# MainBoard.net
KiCad netlist of a schematic drawn in EAGLE
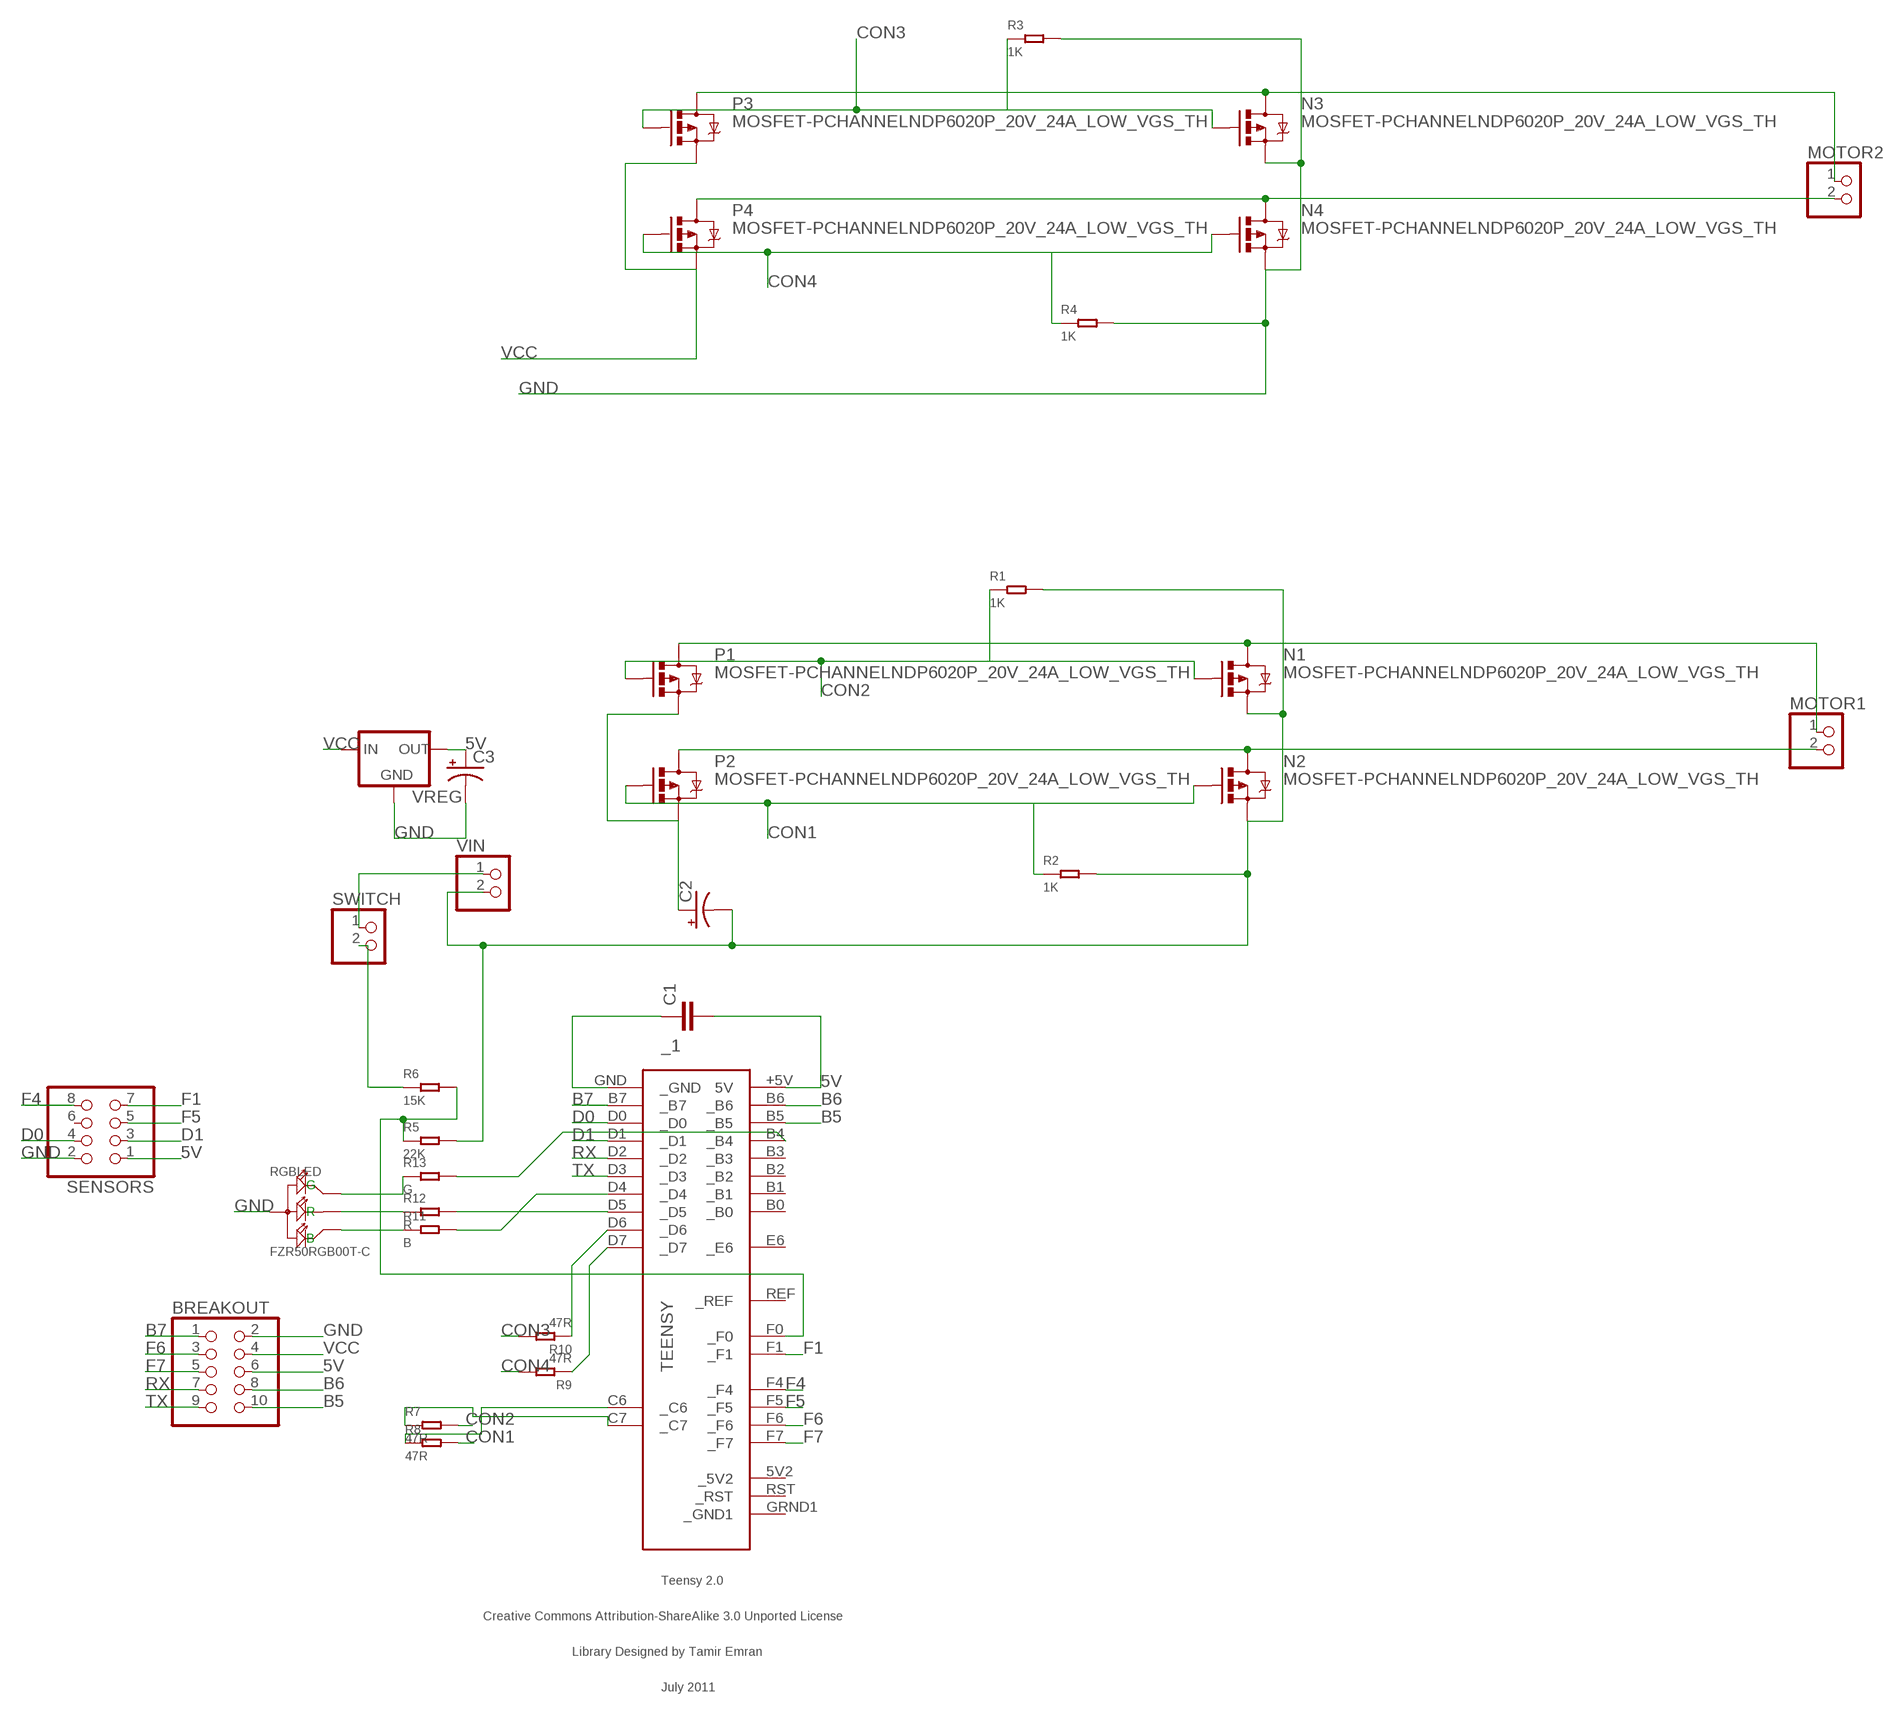
[diagram p0: schematic, sheet 1]

(export (version "E")
  (design (tool "Eeschema 10.0.6"))
  (components
    (comp (ref "BREAKOUT")
      (value "PINHD-2X5")
      (footprint "eagle-import:2X05")
      (libsource (lib "eagle-import") (part "PINHD-2X5"))
    )
    (comp (ref "C1")
      (value "CAPPTH")
      (footprint "eagle-import:CAP-PTH-SMALL")
      (libsource (lib "eagle-import") (part "CAPPTH"))
    )
    (comp (ref "C2")
      (value "CAP_POLPTH2")
      (footprint "eagle-import:CPOL-RADIAL-10UF-25V")
      (libsource (lib "eagle-import") (part "CAP_POLPTH2"))
    )
    (comp (ref "C3")
      (value "CAP_POLPTH2")
      (footprint "eagle-import:CPOL-RADIAL-10UF-25V")
      (libsource (lib "eagle-import") (part "CAP_POLPTH2"))
    )
    (comp (ref "MOTOR1")
      (value "PINHD-1X2")
      (footprint "eagle-import:1X02")
      (libsource (lib "eagle-import") (part "PINHD-1X2"))
    )
    (comp (ref "MOTOR2")
      (value "PINHD-1X2")
      (footprint "eagle-import:1X02")
      (libsource (lib "eagle-import") (part "PINHD-1X2"))
    )
    (comp (ref "N1")
      (value "MOSFET-PCHANNELNDP6020P_20V_24A_LOW_VGS_TH")
      (footprint "eagle-import:TO220V")
      (libsource (lib "eagle-import") (part "MOSFET-PCHANNELNDP6020P_20V_24A_LOW_VGS_TH"))
    )
    (comp (ref "N2")
      (value "MOSFET-PCHANNELNDP6020P_20V_24A_LOW_VGS_TH")
      (footprint "eagle-import:TO220V")
      (libsource (lib "eagle-import") (part "MOSFET-PCHANNELNDP6020P_20V_24A_LOW_VGS_TH"))
    )
    (comp (ref "N3")
      (value "MOSFET-PCHANNELNDP6020P_20V_24A_LOW_VGS_TH")
      (footprint "eagle-import:TO220V")
      (libsource (lib "eagle-import") (part "MOSFET-PCHANNELNDP6020P_20V_24A_LOW_VGS_TH"))
    )
    (comp (ref "N4")
      (value "MOSFET-PCHANNELNDP6020P_20V_24A_LOW_VGS_TH")
      (footprint "eagle-import:TO220V")
      (libsource (lib "eagle-import") (part "MOSFET-PCHANNELNDP6020P_20V_24A_LOW_VGS_TH"))
    )
    (comp (ref "P1")
      (value "MOSFET-PCHANNELNDP6020P_20V_24A_LOW_VGS_TH")
      (footprint "eagle-import:TO220V")
      (libsource (lib "eagle-import") (part "MOSFET-PCHANNELNDP6020P_20V_24A_LOW_VGS_TH"))
    )
    (comp (ref "P2")
      (value "MOSFET-PCHANNELNDP6020P_20V_24A_LOW_VGS_TH")
      (footprint "eagle-import:TO220V")
      (libsource (lib "eagle-import") (part "MOSFET-PCHANNELNDP6020P_20V_24A_LOW_VGS_TH"))
    )
    (comp (ref "P3")
      (value "MOSFET-PCHANNELNDP6020P_20V_24A_LOW_VGS_TH")
      (footprint "eagle-import:TO220V")
      (libsource (lib "eagle-import") (part "MOSFET-PCHANNELNDP6020P_20V_24A_LOW_VGS_TH"))
    )
    (comp (ref "P4")
      (value "MOSFET-PCHANNELNDP6020P_20V_24A_LOW_VGS_TH")
      (footprint "eagle-import:TO220V")
      (libsource (lib "eagle-import") (part "MOSFET-PCHANNELNDP6020P_20V_24A_LOW_VGS_TH"))
    )
    (comp (ref "R1")
      (value "1K")
      (footprint "eagle-import:PR-D2.3XL6.5MM")
      (fields (field (name "MPN") "FHCFR-1/4W-102J"))
      (libsource (lib "eagle-import") (part "DIP-RES-1K-5%-1/4W(PR-D2.3XL6.5MM)"))
    )
    (comp (ref "R2")
      (value "1K")
      (footprint "eagle-import:PR-D2.3XL6.5MM")
      (fields (field (name "MPN") "FHCFR-1/4W-102J"))
      (libsource (lib "eagle-import") (part "DIP-RES-1K-5%-1/4W(PR-D2.3XL6.5MM)"))
    )
    (comp (ref "R3")
      (value "1K")
      (footprint "eagle-import:PR-D2.3XL6.5MM")
      (fields (field (name "MPN") "FHCFR-1/4W-102J"))
      (libsource (lib "eagle-import") (part "DIP-RES-1K-5%-1/4W(PR-D2.3XL6.5MM)"))
    )
    (comp (ref "R4")
      (value "1K")
      (footprint "eagle-import:PR-D2.3XL6.5MM")
      (fields (field (name "MPN") "FHCFR-1/4W-102J"))
      (libsource (lib "eagle-import") (part "DIP-RES-1K-5%-1/4W(PR-D2.3XL6.5MM)"))
    )
    (comp (ref "R5")
      (value "22K")
      (footprint "eagle-import:PR-D2.3XL6.5MM")
      (fields (field (name "MPN") "FHCFR-1/4W-223J"))
      (libsource (lib "eagle-import") (part "DIP-RES-22K-5%-1/4W(PR-D2.3XL6.5MM)"))
    )
    (comp (ref "R6")
      (value "15K")
      (footprint "eagle-import:PR-D2.3XL6.5MM")
      (libsource (lib "eagle-import") (part "DIP-RES-10K-5%-1/4W(PR-D2.3XL6.5MM)"))
    )
    (comp (ref "R7")
      (value "47R")
      (footprint "eagle-import:PR-D2.3XL6.5MM")
      (fields (field (name "MPN") "FHCFR-1/4W-470J"))
      (libsource (lib "eagle-import") (part "DIP-RES-47R-5%-1/4W(PR-D2.3XL6.5MM)"))
    )
    (comp (ref "R8")
      (value "47R")
      (footprint "eagle-import:PR-D2.3XL6.5MM")
      (fields (field (name "MPN") "FHCFR-1/4W-470J"))
      (libsource (lib "eagle-import") (part "DIP-RES-47R-5%-1/4W(PR-D2.3XL6.5MM)"))
    )
    (comp (ref "R9")
      (value "47R")
      (footprint "eagle-import:PR-D2.3XL6.5MM")
      (fields (field (name "MPN") "FHCFR-1/4W-470J"))
      (libsource (lib "eagle-import") (part "DIP-RES-47R-5%-1/4W(PR-D2.3XL6.5MM)"))
    )
    (comp (ref "R10")
      (value "47R")
      (footprint "eagle-import:PR-D2.3XL6.5MM")
      (fields (field (name "MPN") "FHCFR-1/4W-470J"))
      (libsource (lib "eagle-import") (part "DIP-RES-47R-5%-1/4W(PR-D2.3XL6.5MM)"))
    )
    (comp (ref "R11")
      (value "B")
      (footprint "eagle-import:PR-D2.3XL6.5MM")
      (fields (field (name "MPN") "FHCFR-1/4W-223J"))
      (libsource (lib "eagle-import") (part "DIP-RES-22K-5%-1/4W(PR-D2.3XL6.5MM)"))
    )
    (comp (ref "R12")
      (value "R")
      (footprint "eagle-import:PR-D2.3XL6.5MM")
      (fields (field (name "MPN") "FHCFR-1/4W-223J"))
      (libsource (lib "eagle-import") (part "DIP-RES-22K-5%-1/4W(PR-D2.3XL6.5MM)"))
    )
    (comp (ref "R13")
      (value "G")
      (footprint "eagle-import:PR-D2.3XL6.5MM")
      (fields (field (name "MPN") "FHCFR-1/4W-223J"))
      (libsource (lib "eagle-import") (part "DIP-RES-22K-5%-1/4W(PR-D2.3XL6.5MM)"))
    )
    (comp (ref "RGBLED")
      (value "FZR50RGB00T-C")
      (footprint "eagle-import:LED4-1.3-D5.0MM")
      (libsource (lib "eagle-import") (part "DIP-LED-RGB-COMMON-ANODE(4P-D5MM)"))
    )
    (comp (ref "SENSORS")
      (value "PINHD-2X4")
      (footprint "eagle-import:2X04")
      (libsource (lib "eagle-import") (part "PINHD-2X4"))
    )
    (comp (ref "SWITCH")
      (value "PINHD-1X2")
      (footprint "eagle-import:1X02")
      (libsource (lib "eagle-import") (part "PINHD-1X2"))
    )
    (comp (ref "VIN")
      (value "PINHD-1X2")
      (footprint "eagle-import:1X02")
      (libsource (lib "eagle-import") (part "PINHD-1X2"))
    )
    (comp (ref "VREG")
      (value "V_REG_78XXSINK")
      (footprint "eagle-import:TO220-IGO")
      (libsource (lib "eagle-import") (part "V_REG_78XXSINK"))
    )
    (comp (ref "_1")
      (value "TEENSY")
      (footprint "eagle-import:TEENSY")
      (libsource (lib "eagle-import") (part "TEENSY"))
    )
  )
  (nets
    (net (code "1") (name "/5V") (class "Default")
      (node (ref "BREAKOUT") (pin "6") (pinfunction "6_6") (pintype "passive"))
      (node (ref "C1") (pin "2") (pinfunction "2_2") (pintype "passive"))
      (node (ref "C3") (pin "1") (pinfunction "+_1") (pintype "passive"))
      (node (ref "SENSORS") (pin "1") (pinfunction "1_1") (pintype "passive"))
      (node (ref "VREG") (pin "OUT") (pinfunction "OUT_OUT") (pintype "passive"))
      (node (ref "_1") (pin "+5V") (pinfunction "5V_+5V") (pintype "bidirectional"))
    )
    (net (code "2") (name "/B5") (class "Default")
      (node (ref "BREAKOUT") (pin "10") (pinfunction "10_10") (pintype "passive"))
      (node (ref "_1") (pin "B5") (pinfunction "_B5_B5") (pintype "bidirectional"))
    )
    (net (code "3") (name "/B6") (class "Default")
      (node (ref "BREAKOUT") (pin "8") (pinfunction "8_8") (pintype "passive"))
      (node (ref "_1") (pin "B6") (pinfunction "_B6_B6") (pintype "bidirectional"))
    )
    (net (code "4") (name "/B7") (class "Default")
      (node (ref "BREAKOUT") (pin "1") (pinfunction "1_1") (pintype "passive"))
      (node (ref "_1") (pin "B7") (pinfunction "_B7_B7") (pintype "bidirectional"))
    )
    (net (code "5") (name "/CON1") (class "Default")
      (node (ref "N2") (pin "1") (pinfunction "G_1") (pintype "passive"))
      (node (ref "P2") (pin "1") (pinfunction "G_1") (pintype "passive"))
      (node (ref "R2") (pin "1") (pinfunction "1_1") (pintype "passive"))
      (node (ref "R8") (pin "2") (pinfunction "2_2") (pintype "passive"))
    )
    (net (code "6") (name "/CON2") (class "Default")
      (node (ref "N1") (pin "1") (pinfunction "G_1") (pintype "passive"))
      (node (ref "P1") (pin "1") (pinfunction "G_1") (pintype "passive"))
      (node (ref "R1") (pin "1") (pinfunction "1_1") (pintype "passive"))
      (node (ref "R7") (pin "2") (pinfunction "2_2") (pintype "passive"))
    )
    (net (code "7") (name "/CON3") (class "Default")
      (node (ref "N3") (pin "1") (pinfunction "G_1") (pintype "passive"))
      (node (ref "P3") (pin "1") (pinfunction "G_1") (pintype "passive"))
      (node (ref "R10") (pin "2") (pinfunction "2_2") (pintype "passive"))
      (node (ref "R3") (pin "1") (pinfunction "1_1") (pintype "passive"))
    )
    (net (code "8") (name "/CON4") (class "Default")
      (node (ref "N4") (pin "1") (pinfunction "G_1") (pintype "passive"))
      (node (ref "P4") (pin "1") (pinfunction "G_1") (pintype "passive"))
      (node (ref "R4") (pin "1") (pinfunction "1_1") (pintype "passive"))
      (node (ref "R9") (pin "2") (pinfunction "2_2") (pintype "passive"))
    )
    (net (code "9") (name "/D0") (class "Default")
      (node (ref "SENSORS") (pin "4") (pinfunction "4_4") (pintype "passive"))
      (node (ref "_1") (pin "D0") (pinfunction "_D0_D0") (pintype "bidirectional"))
    )
    (net (code "10") (name "/D1") (class "Default")
      (node (ref "SENSORS") (pin "3") (pinfunction "3_3") (pintype "passive"))
      (node (ref "_1") (pin "D1") (pinfunction "_D1_D1") (pintype "bidirectional"))
    )
    (net (code "11") (name "/F1") (class "Default")
      (node (ref "SENSORS") (pin "7") (pinfunction "7_7") (pintype "passive"))
      (node (ref "_1") (pin "F1") (pinfunction "_F1_F1") (pintype "bidirectional"))
    )
    (net (code "12") (name "/F4") (class "Default")
      (node (ref "SENSORS") (pin "8") (pinfunction "8_8") (pintype "passive"))
      (node (ref "_1") (pin "F4") (pinfunction "_F4_F4") (pintype "bidirectional"))
    )
    (net (code "13") (name "/F5") (class "Default")
      (node (ref "SENSORS") (pin "5") (pinfunction "5_5") (pintype "passive"))
      (node (ref "_1") (pin "F5") (pinfunction "_F5_F5") (pintype "bidirectional"))
    )
    (net (code "14") (name "/F6") (class "Default")
      (node (ref "BREAKOUT") (pin "3") (pinfunction "3_3") (pintype "passive"))
      (node (ref "_1") (pin "F6") (pinfunction "_F6_F6") (pintype "bidirectional"))
    )
    (net (code "15") (name "/F7") (class "Default")
      (node (ref "BREAKOUT") (pin "5") (pinfunction "5_5") (pintype "passive"))
      (node (ref "_1") (pin "F7") (pinfunction "_F7_F7") (pintype "bidirectional"))
    )
    (net (code "16") (name "/GND") (class "Default")
      (node (ref "BREAKOUT") (pin "2") (pinfunction "2_2") (pintype "passive"))
      (node (ref "C1") (pin "1") (pinfunction "1_1") (pintype "passive"))
      (node (ref "C2") (pin "2") (pinfunction "-_2") (pintype "passive"))
      (node (ref "C3") (pin "2") (pinfunction "-_2") (pintype "passive"))
      (node (ref "N1") (pin "3") (pinfunction "S_3") (pintype "passive"))
      (node (ref "N2") (pin "3") (pinfunction "S_3") (pintype "passive"))
      (node (ref "N3") (pin "3") (pinfunction "S_3") (pintype "passive"))
      (node (ref "N4") (pin "3") (pinfunction "S_3") (pintype "passive"))
      (node (ref "R1") (pin "2") (pinfunction "2_2") (pintype "passive"))
      (node (ref "R2") (pin "2") (pinfunction "2_2") (pintype "passive"))
      (node (ref "R3") (pin "2") (pinfunction "2_2") (pintype "passive"))
      (node (ref "R4") (pin "2") (pinfunction "2_2") (pintype "passive"))
      (node (ref "R5") (pin "2") (pinfunction "2_2") (pintype "passive"))
      (node (ref "RGBLED") (pin "C") (pinfunction "+_C") (pintype "bidirectional"))
      (node (ref "SENSORS") (pin "2") (pinfunction "2_2") (pintype "passive"))
      (node (ref "VIN") (pin "2") (pinfunction "2_2") (pintype "passive"))
      (node (ref "VREG") (pin "GND") (pinfunction "GND_GND") (pintype "input"))
      (node (ref "_1") (pin "GND") (pinfunction "_GND_GND") (pintype "bidirectional"))
    )
    (net (code "17") (name "/RX") (class "Default")
      (node (ref "BREAKOUT") (pin "7") (pinfunction "7_7") (pintype "passive"))
      (node (ref "_1") (pin "D2") (pinfunction "_D2_D2") (pintype "bidirectional"))
    )
    (net (code "18") (name "/TX") (class "Default")
      (node (ref "BREAKOUT") (pin "9") (pinfunction "9_9") (pintype "passive"))
      (node (ref "_1") (pin "D3") (pinfunction "_D3_D3") (pintype "bidirectional"))
    )
    (net (code "19") (name "/VCC") (class "Default")
      (node (ref "BREAKOUT") (pin "4") (pinfunction "4_4") (pintype "passive"))
      (node (ref "C2") (pin "1") (pinfunction "+_1") (pintype "passive"))
      (node (ref "P1") (pin "3") (pinfunction "S_3") (pintype "passive"))
      (node (ref "P2") (pin "3") (pinfunction "S_3") (pintype "passive"))
      (node (ref "P3") (pin "3") (pinfunction "S_3") (pintype "passive"))
      (node (ref "P4") (pin "3") (pinfunction "S_3") (pintype "passive"))
      (node (ref "R6") (pin "1") (pinfunction "1_1") (pintype "passive"))
      (node (ref "SWITCH") (pin "2") (pinfunction "2_2") (pintype "passive"))
      (node (ref "VREG") (pin "IN") (pinfunction "IN_IN") (pintype "input"))
    )
    (net (code "20") (name "Net-(N1-D)") (class "Default")
      (node (ref "MOTOR1") (pin "1") (pinfunction "1_1") (pintype "passive"))
      (node (ref "N1") (pin "2") (pinfunction "D_2") (pintype "passive"))
      (node (ref "P1") (pin "2") (pinfunction "D_2") (pintype "passive"))
    )
    (net (code "21") (name "Net-(N2-D)") (class "Default")
      (node (ref "MOTOR1") (pin "2") (pinfunction "2_2") (pintype "passive"))
      (node (ref "N2") (pin "2") (pinfunction "D_2") (pintype "passive"))
      (node (ref "P2") (pin "2") (pinfunction "D_2") (pintype "passive"))
    )
    (net (code "22") (name "Net-(N3-D)") (class "Default")
      (node (ref "MOTOR2") (pin "1") (pinfunction "1_1") (pintype "passive"))
      (node (ref "N3") (pin "2") (pinfunction "D_2") (pintype "passive"))
      (node (ref "P3") (pin "2") (pinfunction "D_2") (pintype "passive"))
    )
    (net (code "23") (name "Net-(N4-D)") (class "Default")
      (node (ref "MOTOR2") (pin "2") (pinfunction "2_2") (pintype "passive"))
      (node (ref "N4") (pin "2") (pinfunction "D_2") (pintype "passive"))
      (node (ref "P4") (pin "2") (pinfunction "D_2") (pintype "passive"))
    )
    (net (code "24") (name "Net-(R11-Pad1)") (class "Default")
      (node (ref "R11") (pin "1") (pinfunction "1_1") (pintype "passive"))
      (node (ref "RGBLED") (pin "B") (pinfunction "B_B") (pintype "bidirectional"))
    )
    (net (code "25") (name "Net-(R12-Pad1)") (class "Default")
      (node (ref "R12") (pin "1") (pinfunction "1_1") (pintype "passive"))
      (node (ref "RGBLED") (pin "R") (pinfunction "R_R") (pintype "bidirectional"))
    )
    (net (code "26") (name "Net-(R13-Pad1)") (class "Default")
      (node (ref "R13") (pin "1") (pinfunction "1_1") (pintype "passive"))
      (node (ref "RGBLED") (pin "G") (pinfunction "G_G") (pintype "bidirectional"))
    )
    (net (code "27") (name "Net-(SWITCH-Pad1)") (class "Default")
      (node (ref "SWITCH") (pin "1") (pinfunction "1_1") (pintype "passive"))
      (node (ref "VIN") (pin "1") (pinfunction "1_1") (pintype "passive"))
    )
    (net (code "28") (name "Net-(_1-_B4)") (class "Default")
      (node (ref "R13") (pin "2") (pinfunction "2_2") (pintype "passive"))
      (node (ref "_1") (pin "B4") (pinfunction "_B4_B4") (pintype "bidirectional"))
    )
    (net (code "29") (name "Net-(_1-_C6)") (class "Default")
      (node (ref "R8") (pin "1") (pinfunction "1_1") (pintype "passive"))
      (node (ref "_1") (pin "C6") (pinfunction "_C6_C6") (pintype "bidirectional"))
    )
    (net (code "30") (name "Net-(_1-_C7)") (class "Default")
      (node (ref "R7") (pin "1") (pinfunction "1_1") (pintype "passive"))
      (node (ref "_1") (pin "C7") (pinfunction "_C7_C7") (pintype "bidirectional"))
    )
    (net (code "31") (name "Net-(_1-_D4)") (class "Default")
      (node (ref "R11") (pin "2") (pinfunction "2_2") (pintype "passive"))
      (node (ref "_1") (pin "D4") (pinfunction "_D4_D4") (pintype "bidirectional"))
    )
    (net (code "32") (name "Net-(_1-_D5)") (class "Default")
      (node (ref "R12") (pin "2") (pinfunction "2_2") (pintype "passive"))
      (node (ref "_1") (pin "D5") (pinfunction "_D5_D5") (pintype "bidirectional"))
    )
    (net (code "33") (name "Net-(_1-_D6)") (class "Default")
      (node (ref "R10") (pin "1") (pinfunction "1_1") (pintype "passive"))
      (node (ref "_1") (pin "D6") (pinfunction "_D6_D6") (pintype "bidirectional"))
    )
    (net (code "34") (name "Net-(_1-_D7)") (class "Default")
      (node (ref "R9") (pin "1") (pinfunction "1_1") (pintype "passive"))
      (node (ref "_1") (pin "D7") (pinfunction "_D7_D7") (pintype "bidirectional"))
    )
    (net (code "35") (name "Net-(_1-_F0)") (class "Default")
      (node (ref "R5") (pin "1") (pinfunction "1_1") (pintype "passive"))
      (node (ref "R6") (pin "2") (pinfunction "2_2") (pintype "passive"))
      (node (ref "_1") (pin "F0") (pinfunction "_F0_F0") (pintype "bidirectional"))
    )
    (net (code "36") (name "unconnected-(SENSORS-Pad6)") (class "Default")
      (node (ref "SENSORS") (pin "6") (pinfunction "6_6") (pintype "passive"))
    )
    (net (code "37") (name "unconnected-(_1-_5V2-Pad5V2)") (class "Default")
      (node (ref "_1") (pin "5V2") (pinfunction "_5V2_5V2") (pintype "bidirectional"))
    )
    (net (code "38") (name "unconnected-(_1-_B0-PadB0)") (class "Default")
      (node (ref "_1") (pin "B0") (pinfunction "_B0_B0") (pintype "bidirectional"))
    )
    (net (code "39") (name "unconnected-(_1-_B1-PadB1)") (class "Default")
      (node (ref "_1") (pin "B1") (pinfunction "_B1_B1") (pintype "bidirectional"))
    )
    (net (code "40") (name "unconnected-(_1-_B2-PadB2)") (class "Default")
      (node (ref "_1") (pin "B2") (pinfunction "_B2_B2") (pintype "bidirectional"))
    )
    (net (code "41") (name "unconnected-(_1-_B3-PadB3)") (class "Default")
      (node (ref "_1") (pin "B3") (pinfunction "_B3_B3") (pintype "bidirectional"))
    )
    (net (code "42") (name "unconnected-(_1-_E6-PadE6)") (class "Default")
      (node (ref "_1") (pin "E6") (pinfunction "_E6_E6") (pintype "bidirectional"))
    )
    (net (code "43") (name "unconnected-(_1-_GND1-PadGRND1)") (class "Default")
      (node (ref "_1") (pin "GRND1") (pinfunction "_GND1_GRND1") (pintype "bidirectional"))
    )
    (net (code "44") (name "unconnected-(_1-_REF-PadREF)") (class "Default")
      (node (ref "_1") (pin "REF") (pinfunction "_REF_REF") (pintype "bidirectional"))
    )
    (net (code "45") (name "unconnected-(_1-_RST-PadRST)") (class "Default")
      (node (ref "_1") (pin "RST") (pinfunction "_RST_RST") (pintype "bidirectional"))
    )
  )
)
